# mssaPIC12.net
KiCad netlist of a schematic drawn in EAGLE
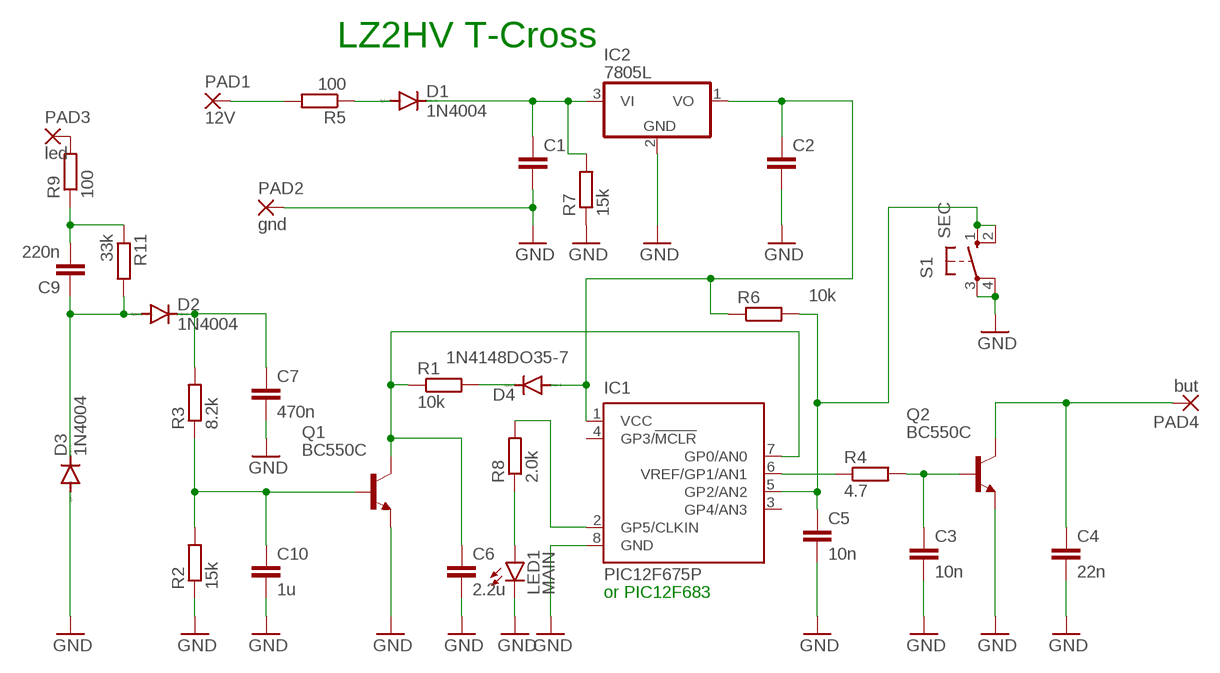
[diagram p0: schematic, sheet 1]

(export (version "E")
  (design (tool "Eeschema 10.0.6"))
  (components
    (comp (ref "C1")
      (value "100n")
      (footprint "eagle-import:C5B2.5")
      (libsource (lib "eagle-import") (part "C5/2.5"))
    )
    (comp (ref "C2")
      (value "101n")
      (footprint "eagle-import:C5B2.5")
      (libsource (lib "eagle-import") (part "C5/2.5"))
    )
    (comp (ref "C3")
      (value "10n")
      (footprint "eagle-import:C5B2.5")
      (libsource (lib "eagle-import") (part "C5/2.5"))
    )
    (comp (ref "C4")
      (value "22n")
      (footprint "eagle-import:C5B2.5")
      (libsource (lib "eagle-import") (part "C5/2.5"))
    )
    (comp (ref "C5")
      (value "10n")
      (footprint "eagle-import:C5B2.5")
      (libsource (lib "eagle-import") (part "C5/2.5"))
    )
    (comp (ref "C6")
      (value "2.2u")
      (footprint "eagle-import:C5B2.5")
      (libsource (lib "eagle-import") (part "C5/2.5"))
    )
    (comp (ref "C7")
      (value "470n")
      (footprint "eagle-import:C5B2.5")
      (libsource (lib "eagle-import") (part "C5/2.5"))
    )
    (comp (ref "C9")
      (value "220n")
      (footprint "eagle-import:C5B2.5")
      (libsource (lib "eagle-import") (part "C5/2.5"))
    )
    (comp (ref "C10")
      (value "1u")
      (footprint "eagle-import:C5B2.5")
      (libsource (lib "eagle-import") (part "C5/2.5"))
    )
    (comp (ref "D1")
      (value "1N4004")
      (footprint "eagle-import:DO41-10")
      (libsource (lib "eagle-import") (part "1N4004"))
    )
    (comp (ref "D2")
      (value "1N4004")
      (footprint "eagle-import:DO41-10")
      (libsource (lib "eagle-import") (part "1N4004"))
    )
    (comp (ref "D3")
      (value "1N4004")
      (footprint "eagle-import:DO41-10")
      (libsource (lib "eagle-import") (part "1N4004"))
    )
    (comp (ref "D4")
      (value "1N4148DO35-7")
      (footprint "eagle-import:DO35-7")
      (libsource (lib "eagle-import") (part "1N4148DO35-7"))
    )
    (comp (ref "IC1")
      (value "PIC12F675P")
      (footprint "eagle-import:DIL8")
      (fields (field (name "MF") "MICROCHIP") (field (name "MPN") "PIC12F675-E/P"))
      (libsource (lib "eagle-import") (part "PIC12F675P"))
    )
    (comp (ref "IC2")
      (value "7805L")
      (footprint "eagle-import:TO92")
      (libsource (lib "eagle-import") (part "78L05"))
    )
    (comp (ref "LED1")
      (value "MAIN")
      (footprint "eagle-import:LED3MM")
      (libsource (lib "eagle-import") (part "LED3MM"))
    )
    (comp (ref "PAD1")
      (value "12V")
      (footprint "eagle-import:2,54_1,0")
      (libsource (lib "eagle-import") (part "2,54/1,0"))
    )
    (comp (ref "PAD2")
      (value "gnd")
      (footprint "eagle-import:2,54_1,0")
      (libsource (lib "eagle-import") (part "2,54/1,0"))
    )
    (comp (ref "PAD3")
      (value "led")
      (footprint "eagle-import:2,54_1,0")
      (libsource (lib "eagle-import") (part "2,54/1,0"))
    )
    (comp (ref "PAD4")
      (value "but")
      (footprint "eagle-import:2,54_1,0")
      (libsource (lib "eagle-import") (part "2,54/1,0"))
    )
    (comp (ref "Q1")
      (value "BC550C")
      (footprint "eagle-import:TO92-EBC")
      (libsource (lib "eagle-import") (part "BC550C"))
    )
    (comp (ref "Q2")
      (value "BC550C")
      (footprint "eagle-import:TO92-EBC")
      (libsource (lib "eagle-import") (part "BC550C"))
    )
    (comp (ref "R1")
      (value "10k")
      (footprint "eagle-import:0207_7")
      (libsource (lib "eagle-import") (part "R-EU_0207/7"))
    )
    (comp (ref "R2")
      (value "15k")
      (footprint "eagle-import:0207_7")
      (libsource (lib "eagle-import") (part "R-EU_0207/7"))
    )
    (comp (ref "R3")
      (value "8.2k")
      (footprint "eagle-import:0207_7")
      (libsource (lib "eagle-import") (part "R-EU_0207/7"))
    )
    (comp (ref "R4")
      (value "4.7")
      (footprint "eagle-import:0207_7")
      (libsource (lib "eagle-import") (part "R-EU_0207/7"))
    )
    (comp (ref "R5")
      (value "100")
      (footprint "eagle-import:0207_7")
      (libsource (lib "eagle-import") (part "R-EU_0207/7"))
    )
    (comp (ref "R6")
      (value "10k")
      (footprint "eagle-import:0207_7")
      (libsource (lib "eagle-import") (part "R-EU_0207/7"))
    )
    (comp (ref "R7")
      (value "15k")
      (footprint "eagle-import:0207_7")
      (libsource (lib "eagle-import") (part "R-EU_0207/7"))
    )
    (comp (ref "R8")
      (value "2.0k")
      (footprint "eagle-import:0207_7")
      (libsource (lib "eagle-import") (part "R-EU_0207/7"))
    )
    (comp (ref "R9")
      (value "100")
      (footprint "eagle-import:0207_2V")
      (libsource (lib "eagle-import") (part "R-EU_0207/2V"))
    )
    (comp (ref "R11")
      (value "33k")
      (footprint "eagle-import:0207_2V")
      (libsource (lib "eagle-import") (part "R-EU_0207/2V"))
    )
    (comp (ref "S1")
      (value "SEC")
      (footprint "eagle-import:B3F-10XX")
      (fields (field (name "MPN") "B3F-1000"))
      (libsource (lib "eagle-import") (part "10-XX"))
    )
  )
  (nets
    (net (code "1") (name "GND") (class "Default")
      (node (ref "C1") (pin "2") (pinfunction "2_2") (pintype "passive"))
      (node (ref "C10") (pin "2") (pinfunction "2_2") (pintype "passive"))
      (node (ref "C2") (pin "2") (pinfunction "2_2") (pintype "passive"))
      (node (ref "C3") (pin "2") (pinfunction "2_2") (pintype "passive"))
      (node (ref "C4") (pin "2") (pinfunction "2_2") (pintype "passive"))
      (node (ref "C5") (pin "2") (pinfunction "2_2") (pintype "passive"))
      (node (ref "C6") (pin "2") (pinfunction "2_2") (pintype "passive"))
      (node (ref "C7") (pin "2") (pinfunction "2_2") (pintype "passive"))
      (node (ref "D3") (pin "A") (pinfunction "A_A") (pintype "passive"))
      (node (ref "IC1") (pin "8") (pinfunction "GND_8") (pintype "power_in"))
      (node (ref "IC2") (pin "2") (pinfunction "GND_2") (pintype "passive"))
      (node (ref "LED1") (pin "K") (pinfunction "C_K") (pintype "passive"))
      (node (ref "PAD2") (pin "1") (pinfunction "P_1") (pintype "passive"))
      (node (ref "Q1") (pin "E") (pinfunction "E_E") (pintype "passive"))
      (node (ref "Q2") (pin "E") (pinfunction "E_E") (pintype "passive"))
      (node (ref "R2") (pin "1") (pinfunction "1_1") (pintype "passive"))
      (node (ref "R7") (pin "1") (pinfunction "1_1") (pintype "passive"))
      (node (ref "S1") (pin "3") (pinfunction "P_3") (pintype "passive"))
      (node (ref "S1") (pin "4") (pinfunction "P1_4") (pintype "passive"))
    )
    (net (code "2") (name "Net-(C3-Pad1)") (class "Default")
      (node (ref "C3") (pin "1") (pinfunction "1_1") (pintype "passive"))
      (node (ref "Q2") (pin "B") (pinfunction "B_B") (pintype "passive"))
      (node (ref "R4") (pin "2") (pinfunction "2_2") (pintype "passive"))
    )
    (net (code "3") (name "Net-(C7-Pad1)") (class "Default")
      (node (ref "C7") (pin "1") (pinfunction "1_1") (pintype "passive"))
      (node (ref "D2") (pin "C") (pinfunction "C_C") (pintype "passive"))
      (node (ref "R3") (pin "2") (pinfunction "2_2") (pintype "passive"))
    )
    (net (code "4") (name "Net-(C9-Pad1)") (class "Default")
      (node (ref "C9") (pin "1") (pinfunction "1_1") (pintype "passive"))
      (node (ref "D2") (pin "A") (pinfunction "A_A") (pintype "passive"))
      (node (ref "D3") (pin "C") (pinfunction "C_C") (pintype "passive"))
      (node (ref "R11") (pin "2") (pinfunction "2_2") (pintype "passive"))
    )
    (net (code "5") (name "Net-(C9-Pad2)") (class "Default")
      (node (ref "C9") (pin "2") (pinfunction "2_2") (pintype "passive"))
      (node (ref "R11") (pin "1") (pinfunction "1_1") (pintype "passive"))
      (node (ref "R9") (pin "1") (pinfunction "1_1") (pintype "passive"))
    )
    (net (code "6") (name "Net-(C10-Pad1)") (class "Default")
      (node (ref "C10") (pin "1") (pinfunction "1_1") (pintype "passive"))
      (node (ref "Q1") (pin "B") (pinfunction "B_B") (pintype "passive"))
      (node (ref "R2") (pin "2") (pinfunction "2_2") (pintype "passive"))
      (node (ref "R3") (pin "1") (pinfunction "1_1") (pintype "passive"))
    )
    (net (code "7") (name "Net-(D1-PadA)") (class "Default")
      (node (ref "D1") (pin "A") (pinfunction "A_A") (pintype "passive"))
      (node (ref "R5") (pin "1") (pinfunction "1_1") (pintype "passive"))
    )
    (net (code "8") (name "Net-(D4-PadC)") (class "Default")
      (node (ref "D4") (pin "C") (pinfunction "C_C") (pintype "passive"))
      (node (ref "R1") (pin "2") (pinfunction "2_2") (pintype "passive"))
    )
    (net (code "9") (name "Net-(IC1-GP0{slash}AN0)") (class "Default")
      (node (ref "C6") (pin "1") (pinfunction "1_1") (pintype "passive"))
      (node (ref "IC1") (pin "7") (pinfunction "GP0/AN0_7") (pintype "bidirectional"))
      (node (ref "Q1") (pin "C") (pinfunction "C_C") (pintype "passive"))
      (node (ref "R1") (pin "1") (pinfunction "1_1") (pintype "passive"))
    )
    (net (code "10") (name "Net-(IC1-GP2{slash}AN2)") (class "Default")
      (node (ref "C5") (pin "1") (pinfunction "1_1") (pintype "passive"))
      (node (ref "IC1") (pin "5") (pinfunction "GP2/AN2_5") (pintype "bidirectional"))
      (node (ref "R6") (pin "2") (pinfunction "2_2") (pintype "passive"))
      (node (ref "S1") (pin "1") (pinfunction "S_1") (pintype "passive"))
      (node (ref "S1") (pin "2") (pinfunction "S1_2") (pintype "passive"))
    )
    (net (code "11") (name "Net-(IC1-GP5{slash}CLKIN)") (class "Default")
      (node (ref "IC1") (pin "2") (pinfunction "GP5/CLKIN_2") (pintype "bidirectional"))
      (node (ref "R8") (pin "2") (pinfunction "2_2") (pintype "passive"))
    )
    (net (code "12") (name "Net-(IC1-VCC)") (class "Default")
      (node (ref "C2") (pin "1") (pinfunction "1_1") (pintype "passive"))
      (node (ref "D4") (pin "A") (pinfunction "A_A") (pintype "passive"))
      (node (ref "IC1") (pin "1") (pinfunction "VCC_1") (pintype "power_in"))
      (node (ref "IC2") (pin "1") (pinfunction "VO_1") (pintype "passive"))
      (node (ref "R6") (pin "1") (pinfunction "1_1") (pintype "passive"))
    )
    (net (code "13") (name "Net-(IC1-VREF{slash}GP1{slash}AN1)") (class "Default")
      (node (ref "IC1") (pin "6") (pinfunction "VREF/GP1/AN1_6") (pintype "bidirectional"))
      (node (ref "R4") (pin "1") (pinfunction "1_1") (pintype "passive"))
    )
    (net (code "14") (name "Net-(IC2-VI)") (class "Default")
      (node (ref "C1") (pin "1") (pinfunction "1_1") (pintype "passive"))
      (node (ref "D1") (pin "C") (pinfunction "C_C") (pintype "passive"))
      (node (ref "IC2") (pin "3") (pinfunction "VI_3") (pintype "input"))
      (node (ref "R7") (pin "2") (pinfunction "2_2") (pintype "passive"))
    )
    (net (code "15") (name "Net-(LED1-PadA)") (class "Default")
      (node (ref "LED1") (pin "A") (pinfunction "A_A") (pintype "passive"))
      (node (ref "R8") (pin "1") (pinfunction "1_1") (pintype "passive"))
    )
    (net (code "16") (name "Net-(PAD1-P)") (class "Default")
      (node (ref "PAD1") (pin "1") (pinfunction "P_1") (pintype "passive"))
      (node (ref "R5") (pin "2") (pinfunction "2_2") (pintype "passive"))
    )
    (net (code "17") (name "Net-(PAD3-P)") (class "Default")
      (node (ref "PAD3") (pin "1") (pinfunction "P_1") (pintype "passive"))
      (node (ref "R9") (pin "2") (pinfunction "2_2") (pintype "passive"))
    )
    (net (code "18") (name "Net-(PAD4-P)") (class "Default")
      (node (ref "C4") (pin "1") (pinfunction "1_1") (pintype "passive"))
      (node (ref "PAD4") (pin "1") (pinfunction "P_1") (pintype "passive"))
      (node (ref "Q2") (pin "C") (pinfunction "C_C") (pintype "passive"))
    )
    (net (code "19") (name "unconnected-(IC1-GP3{slash}~{MCLR}-Pad4)") (class "Default")
      (node (ref "IC1") (pin "4") (pinfunction "GP3/~{MCLR}_4") (pintype "input"))
    )
    (net (code "20") (name "unconnected-(IC1-GP4{slash}AN3-Pad3)") (class "Default")
      (node (ref "IC1") (pin "3") (pinfunction "GP4/AN3_3") (pintype "bidirectional"))
    )
  )
)
